# Sheet_1_2025-06-27.net
KiCad netlist of a schematic drawn in Altium Designer
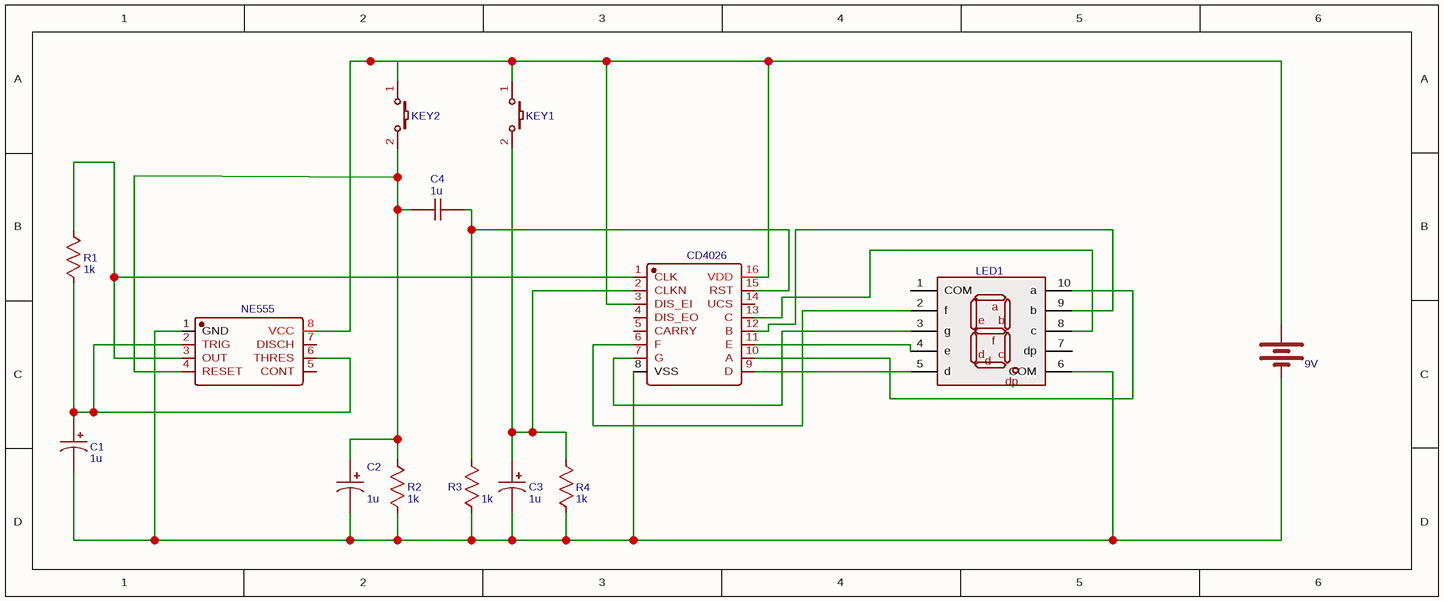
[diagram p0: Sheet_1_2025-06-27.schdoc]

(export (version "E")
  (design (tool "Eeschema 10.0.6"))
  (components
    (comp (ref "BT1")
      (value "9V")
      (fields
        (field (name "MANUFACTURER") "Q&J")
        (field (name "MANUFACTURER PART") "9V电池铜线扣 铜100mm")
        (field (name "CONTRIBUTOR") "lcsc")
      )
      (libsource (lib "altium-import") (part "root_3_9V_"))
    )
    (comp (ref "C1")
      (value "1u")
      (fields (field (name "CONTRIBUTOR") "LCEDA_Lib"))
      (libsource (lib "altium-import") (part "root_3_1u_"))
    )
    (comp (ref "C2")
      (value "1u")
      (fields (field (name "CONTRIBUTOR") "LCEDA_Lib"))
      (libsource (lib "altium-import") (part "root_3_1u_"))
    )
    (comp (ref "C3")
      (value "1u")
      (fields (field (name "CONTRIBUTOR") "LCEDA_Lib"))
      (libsource (lib "altium-import") (part "root_3_1u_"))
    )
    (comp (ref "C4")
      (value "1u")
      (fields (field (name "CONTRIBUTOR") "LCEDA_Lib"))
      (libsource (lib "altium-import") (part "root_0_1u_"))
    )
    (comp (ref "KEY1")
      (value "K2-3.6×6.1_SMD")
      (fields (field (name "MANUFACTURER PART") "K2-1107ST-A4SW-06") (field (name "CONTRIBUTOR") "LCEDA_Lib"))
      (libsource (lib "altium-import") (part "root_3_K2-3.6×6.1_SMD_"))
    )
    (comp (ref "KEY2")
      (value "K2-3.6×6.1_SMD")
      (fields (field (name "MANUFACTURER PART") "K2-1107ST-A4SW-06") (field (name "CONTRIBUTOR") "LCEDA_Lib"))
      (libsource (lib "altium-import") (part "root_3_K2-3.6×6.1_SMD_"))
    )
    (comp (ref "LED1")
      (value "FJ3161BH")
      (fields (field (name "MANUFACTURER") "志浩"))
      (libsource (lib "altium-import") (part "root_0_FJ3161BH_"))
    )
    (comp (ref "R1")
      (value "1k")
      (fields (field (name "CONTRIBUTOR") "LCEDA_Lib"))
      (libsource (lib "altium-import") (part "root_1_1k_"))
    )
    (comp (ref "R2")
      (value "1k")
      (fields (field (name "CONTRIBUTOR") "LCEDA_Lib"))
      (libsource (lib "altium-import") (part "root_1_1k_"))
    )
    (comp (ref "R3")
      (value "1k")
      (fields (field (name "CONTRIBUTOR") "LCEDA_Lib"))
      (libsource (lib "altium-import") (part "root_1_1k_"))
    )
    (comp (ref "R4")
      (value "1k")
      (fields (field (name "CONTRIBUTOR") "LCEDA_Lib"))
      (libsource (lib "altium-import") (part "root_1_1k_"))
    )
    (comp (ref "U1")
      (value "NE555")
      (fields
        (field (name "MANUFACTURER") "TI(德州仪器)")
        (field (name "MANUFACTURER PART") "NE555PE4")
        (field (name "CONTRIBUTOR") "lcsc")
      )
      (libsource (lib "altium-import") (part "root_0_NE555_"))
    )
    (comp (ref "U2")
      (value "CD4026")
      (fields
        (field (name "MANUFACTURER") "LX(灵星芯微)")
        (field (name "MANUFACTURER PART") "CD4026BE(LX)")
        (field (name "CONTRIBUTOR") "lcsc")
      )
      (libsource (lib "altium-import") (part "root_0_CD4026_"))
    )
  )
  (nets
    (net (code "1") (name "Net-(BT1-+)") (class "Default")
      (node (ref "BT1") (pin "1") (pinfunction "+_1") (pintype "passive"))
      (node (ref "KEY1") (pin "1") (pinfunction "1_1") (pintype "passive"))
      (node (ref "KEY2") (pin "1") (pinfunction "1_1") (pintype "passive"))
      (node (ref "U1") (pin "8") (pinfunction "VCC_8") (pintype "passive"))
      (node (ref "U2") (pin "16") (pinfunction "VDD_16") (pintype "passive"))
      (node (ref "U2") (pin "3") (pinfunction "DIS_EI_3") (pintype "passive"))
    )
    (net (code "2") (name "Net-(BT1--)") (class "Default")
      (node (ref "BT1") (pin "2") (pinfunction "-_2") (pintype "passive"))
      (node (ref "C1") (pin "2") (pinfunction "2_2") (pintype "passive"))
      (node (ref "C2") (pin "2") (pinfunction "2_2") (pintype "passive"))
      (node (ref "C3") (pin "2") (pinfunction "2_2") (pintype "passive"))
      (node (ref "LED1") (pin "6") (pinfunction "COM_6") (pintype "passive"))
      (node (ref "R2") (pin "1") (pinfunction "1_1") (pintype "passive"))
      (node (ref "R3") (pin "1") (pinfunction "1_1") (pintype "passive"))
      (node (ref "R4") (pin "1") (pinfunction "1_1") (pintype "passive"))
      (node (ref "U1") (pin "1") (pinfunction "GND_1") (pintype "passive"))
      (node (ref "U2") (pin "8") (pinfunction "VSS_8") (pintype "passive"))
    )
    (net (code "3") (name "Net-(LED1-a)") (class "Default")
      (node (ref "LED1") (pin "10") (pinfunction "a_10") (pintype "passive"))
      (node (ref "U2") (pin "10") (pinfunction "A_10") (pintype "passive"))
    )
    (net (code "4") (name "Net-(LED1-b)") (class "Default")
      (node (ref "LED1") (pin "9") (pinfunction "b_9") (pintype "passive"))
      (node (ref "U2") (pin "12") (pinfunction "B_12") (pintype "passive"))
    )
    (net (code "5") (name "Net-(LED1-c)") (class "Default")
      (node (ref "LED1") (pin "8") (pinfunction "c_8") (pintype "passive"))
      (node (ref "U2") (pin "13") (pinfunction "C_13") (pintype "passive"))
    )
    (net (code "6") (name "Net-(LED1-d)") (class "Default")
      (node (ref "LED1") (pin "5") (pinfunction "d_5") (pintype "passive"))
      (node (ref "U2") (pin "9") (pinfunction "D_9") (pintype "passive"))
    )
    (net (code "7") (name "Net-(LED1-e)") (class "Default")
      (node (ref "LED1") (pin "4") (pinfunction "e_4") (pintype "passive"))
      (node (ref "U2") (pin "11") (pinfunction "E_11") (pintype "passive"))
    )
    (net (code "8") (name "Net-(LED1-f)") (class "Default")
      (node (ref "LED1") (pin "2") (pinfunction "f_2") (pintype "passive"))
      (node (ref "U2") (pin "6") (pinfunction "F_6") (pintype "passive"))
    )
    (net (code "9") (name "Net-(LED1-g)") (class "Default")
      (node (ref "LED1") (pin "3") (pinfunction "g_3") (pintype "passive"))
      (node (ref "U2") (pin "7") (pinfunction "G_7") (pintype "passive"))
    )
    (net (code "10") (name "Net-(U1-OUT)") (class "Default")
      (node (ref "R1") (pin "2") (pinfunction "2_2") (pintype "passive"))
      (node (ref "U1") (pin "3") (pinfunction "OUT_3") (pintype "passive"))
      (node (ref "U2") (pin "1") (pinfunction "CLK_1") (pintype "passive"))
    )
    (net (code "11") (name "Net-(U1-RESET)") (class "Default")
      (node (ref "C2") (pin "1") (pinfunction "1_1") (pintype "passive"))
      (node (ref "C4") (pin "1") (pinfunction "1_1") (pintype "passive"))
      (node (ref "KEY2") (pin "2") (pinfunction "2_2") (pintype "passive"))
      (node (ref "R2") (pin "2") (pinfunction "2_2") (pintype "passive"))
      (node (ref "U1") (pin "4") (pinfunction "RESET_4") (pintype "passive"))
    )
    (net (code "12") (name "Net-(U1-THRES)") (class "Default")
      (node (ref "C1") (pin "1") (pinfunction "1_1") (pintype "passive"))
      (node (ref "R1") (pin "1") (pinfunction "1_1") (pintype "passive"))
      (node (ref "U1") (pin "2") (pinfunction "TRIG_2") (pintype "passive"))
      (node (ref "U1") (pin "6") (pinfunction "THRES_6") (pintype "passive"))
    )
    (net (code "13") (name "Net-(U2-CLKN)") (class "Default")
      (node (ref "C3") (pin "1") (pinfunction "1_1") (pintype "passive"))
      (node (ref "KEY1") (pin "2") (pinfunction "2_2") (pintype "passive"))
      (node (ref "R4") (pin "2") (pinfunction "2_2") (pintype "passive"))
      (node (ref "U2") (pin "2") (pinfunction "CLKN_2") (pintype "passive"))
    )
    (net (code "14") (name "Net-(U2-RST)") (class "Default")
      (node (ref "C4") (pin "2") (pinfunction "2_2") (pintype "passive"))
      (node (ref "R3") (pin "2") (pinfunction "2_2") (pintype "passive"))
      (node (ref "U2") (pin "15") (pinfunction "RST_15") (pintype "passive"))
    )
    (net (code "15") (name "unconnected-(LED1-COM-Pad1)") (class "Default")
      (node (ref "LED1") (pin "1") (pinfunction "COM_1") (pintype "passive"))
    )
    (net (code "16") (name "unconnected-(LED1-dp-Pad7)") (class "Default")
      (node (ref "LED1") (pin "7") (pinfunction "dp_7") (pintype "passive"))
    )
    (net (code "17") (name "unconnected-(U1-CONT-Pad5)") (class "Default")
      (node (ref "U1") (pin "5") (pinfunction "CONT_5") (pintype "passive"))
    )
    (net (code "18") (name "unconnected-(U1-DISCH-Pad7)") (class "Default")
      (node (ref "U1") (pin "7") (pinfunction "DISCH_7") (pintype "passive"))
    )
    (net (code "19") (name "unconnected-(U2-CARRY-Pad5)") (class "Default")
      (node (ref "U2") (pin "5") (pinfunction "CARRY_5") (pintype "passive"))
    )
    (net (code "20") (name "unconnected-(U2-DIS_EO-Pad4)") (class "Default")
      (node (ref "U2") (pin "4") (pinfunction "DIS_EO_4") (pintype "passive"))
    )
    (net (code "21") (name "unconnected-(U2-UCS-Pad14)") (class "Default")
      (node (ref "U2") (pin "14") (pinfunction "UCS_14") (pintype "passive"))
    )
  )
)
